# KHNfilter.net
KiCad netlist of a schematic drawn in Altium Designer
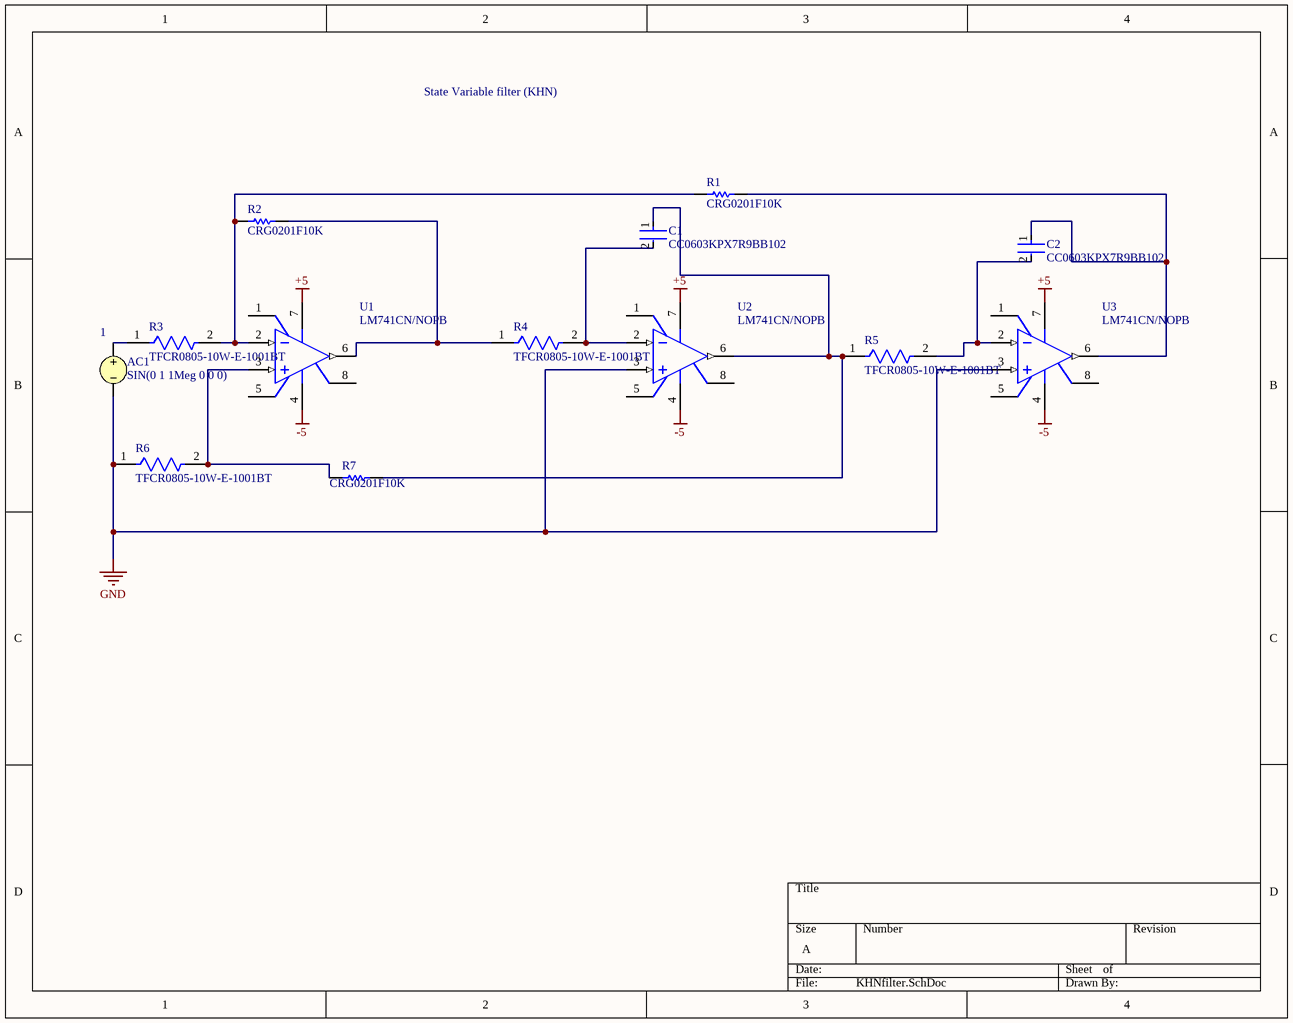
[diagram p0: KHNfilter.SchDoc]

(export (version "E")
  (design (tool "Eeschema 10.0.6"))
  (components
    (comp (ref "AC1")
      (value "SIN(0 1 1Meg 0 0 0)")
      (description "Voltage Source")
      (fields (field (name "AC MAGNITUDE") "1") (field (name "PUBLISHER") "Altium Limited"))
      (libsource (lib "Simulation Generic Components") (part "VSRC"))
    )
    (comp (ref "C1")
      (value "CC0603KPX7R9BB102")
      (footprint "FP-CC0603-DA-MFG")
      (description "CC0603 1.0 nF X7R 10.00% 50 V")
      (fields (field (name "VOLTAGE") "50 V") (field (name "TOLERANCE") "0.1"))
      (libsource (lib "Altium Content Vault") (part "11868f565c42a9108669ba33697ecf6"))
    )
    (comp (ref "C2")
      (value "CC0603KPX7R9BB102")
      (footprint "FP-CC0603-DA-MFG")
      (description "CC0603 1.0 nF X7R 10.00% 50 V")
      (fields (field (name "VOLTAGE") "50 V") (field (name "TOLERANCE") "0.1"))
      (libsource (lib "Altium Content Vault") (part "11868f565c42a9108669ba33697ecf6"))
    )
    (comp (ref "R1")
      (value "CRG0201F10K")
      (footprint "RESC0603X26X15LL03T05")
      (fields (field (name "MANUFACTURER") "TE Connectivity / AMP"))
      (libsource (lib "Altium Content Vault") (part "RES"))
    )
    (comp (ref "R2")
      (value "CRG0201F10K")
      (footprint "RESC0603X26X15LL03T05")
      (fields (field (name "MANUFACTURER") "TE Connectivity / AMP"))
      (libsource (lib "Altium Content Vault") (part "RES"))
    )
    (comp (ref "R3")
      (value "TFCR0805-10W-E-1001BT")
      (footprint "FP-TFCR0805-IPC_A")
      (description "RES Thin Film,  1kΩ, 0.1%, 0.1W, 25ppm/°C, 0805")
      (libsource (lib "Altium Content Vault") (part "1029c3af85768c4190bb7ad29bc67b5"))
    )
    (comp (ref "R4")
      (value "TFCR0805-10W-E-1001BT")
      (footprint "FP-TFCR0805-IPC_A")
      (description "RES Thin Film,  1kΩ, 0.1%, 0.1W, 25ppm/°C, 0805")
      (libsource (lib "Altium Content Vault") (part "1029c3af85768c4190bb7ad29bc67b5"))
    )
    (comp (ref "R5")
      (value "TFCR0805-10W-E-1001BT")
      (footprint "FP-TFCR0805-IPC_A")
      (description "RES Thin Film,  1kΩ, 0.1%, 0.1W, 25ppm/°C, 0805")
      (libsource (lib "Altium Content Vault") (part "1029c3af85768c4190bb7ad29bc67b5"))
    )
    (comp (ref "R6")
      (value "TFCR0805-10W-E-1001BT")
      (footprint "FP-TFCR0805-IPC_A")
      (description "RES Thin Film,  1kΩ, 0.1%, 0.1W, 25ppm/°C, 0805")
      (libsource (lib "Altium Content Vault") (part "1029c3af85768c4190bb7ad29bc67b5"))
    )
    (comp (ref "R7")
      (value "CRG0201F10K")
      (footprint "RESC0603X26X15LL03T05")
      (fields (field (name "MANUFACTURER") "TE Connectivity / AMP"))
      (libsource (lib "Altium Content Vault") (part "RES"))
    )
    (comp (ref "U1")
      (value "LM741CN/NOPB")
      (footprint "P0008A")
      (description "Operational Amplifier, 8-pin MDIP, Pb-Free")
      (fields (field (name "MANUFACTURER") "Texas Instruments"))
      (libsource (lib "Altium Content Vault") (part "AMP-OPA-LM741-8"))
    )
    (comp (ref "U2")
      (value "LM741CN/NOPB")
      (footprint "P0008A")
      (description "Operational Amplifier, 8-pin MDIP, Pb-Free")
      (fields (field (name "MANUFACTURER") "Texas Instruments"))
      (libsource (lib "Altium Content Vault") (part "AMP-OPA-LM741-8"))
    )
    (comp (ref "U3")
      (value "LM741CN/NOPB")
      (footprint "P0008A")
      (description "Operational Amplifier, 8-pin MDIP, Pb-Free")
      (fields (field (name "MANUFACTURER") "Texas Instruments"))
      (libsource (lib "Altium Content Vault") (part "AMP-OPA-LM741-8"))
    )
  )
  (nets
    (net (code "1") (name "+5") (class "Default")
      (node (ref "U1") (pin "7") (pinfunction "V+_7") (pintype "power_in"))
      (node (ref "U2") (pin "7") (pinfunction "V+_7") (pintype "power_in"))
      (node (ref "U3") (pin "7") (pinfunction "V+_7") (pintype "power_in"))
    )
    (net (code "2") (name "-5") (class "Default")
      (node (ref "U1") (pin "4") (pinfunction "V-_4") (pintype "power_in"))
      (node (ref "U2") (pin "4") (pinfunction "V-_4") (pintype "power_in"))
      (node (ref "U3") (pin "4") (pinfunction "V-_4") (pintype "power_in"))
    )
    (net (code "3") (name "GND") (class "Default")
      (node (ref "AC1") (pin "2") (pinfunction "2_2") (pintype "passive"))
      (node (ref "R6") (pin "1") (pinfunction "1_1") (pintype "passive"))
      (node (ref "U2") (pin "3") (pinfunction "IN+_3") (pintype "input"))
      (node (ref "U3") (pin "3") (pinfunction "IN+_3") (pintype "input"))
    )
    (net (code "4") (name "Net-(AC1-Pad1)") (class "Default")
      (node (ref "AC1") (pin "1") (pinfunction "1_1") (pintype "passive"))
      (node (ref "R3") (pin "1") (pinfunction "1_1") (pintype "passive"))
    )
    (net (code "5") (name "Net-(U1-IN+)") (class "Default")
      (node (ref "R6") (pin "2") (pinfunction "2_2") (pintype "passive"))
      (node (ref "R7") (pin "1") (pinfunction "1_1") (pintype "passive"))
      (node (ref "U1") (pin "3") (pinfunction "IN+_3") (pintype "input"))
    )
    (net (code "6") (name "Net-(U1-IN-)") (class "Default")
      (node (ref "R1") (pin "1") (pinfunction "1_1") (pintype "passive"))
      (node (ref "R2") (pin "1") (pinfunction "1_1") (pintype "passive"))
      (node (ref "R3") (pin "2") (pinfunction "2_2") (pintype "passive"))
      (node (ref "U1") (pin "2") (pinfunction "IN-_2") (pintype "input"))
    )
    (net (code "7") (name "Net-(U1-OUT)") (class "Default")
      (node (ref "R2") (pin "2") (pinfunction "2_2") (pintype "passive"))
      (node (ref "R4") (pin "1") (pinfunction "1_1") (pintype "passive"))
      (node (ref "U1") (pin "6") (pinfunction "OUT_6") (pintype "output"))
    )
    (net (code "8") (name "Net-(U2-IN-)") (class "Default")
      (node (ref "C1") (pin "2") (pinfunction "2_2") (pintype "passive"))
      (node (ref "R4") (pin "2") (pinfunction "2_2") (pintype "passive"))
      (node (ref "U2") (pin "2") (pinfunction "IN-_2") (pintype "input"))
    )
    (net (code "9") (name "Net-(U2-OUT)") (class "Default")
      (node (ref "C1") (pin "1") (pinfunction "1_1") (pintype "passive"))
      (node (ref "R5") (pin "1") (pinfunction "1_1") (pintype "passive"))
      (node (ref "R7") (pin "2") (pinfunction "2_2") (pintype "passive"))
      (node (ref "U2") (pin "6") (pinfunction "OUT_6") (pintype "output"))
    )
    (net (code "10") (name "Net-(U3-IN-)") (class "Default")
      (node (ref "C2") (pin "2") (pinfunction "2_2") (pintype "passive"))
      (node (ref "R5") (pin "2") (pinfunction "2_2") (pintype "passive"))
      (node (ref "U3") (pin "2") (pinfunction "IN-_2") (pintype "input"))
    )
    (net (code "11") (name "Net-(U3-OUT)") (class "Default")
      (node (ref "C2") (pin "1") (pinfunction "1_1") (pintype "passive"))
      (node (ref "R1") (pin "2") (pinfunction "2_2") (pintype "passive"))
      (node (ref "U3") (pin "6") (pinfunction "OUT_6") (pintype "output"))
    )
    (net (code "12") (name "unconnected-(U1-NC-Pad8)") (class "Default")
      (node (ref "U1") (pin "8") (pinfunction "NC_8") (pintype "passive"))
    )
    (net (code "13") (name "unconnected-(U1-OFS_NULL-Pad1)") (class "Default")
      (node (ref "U1") (pin "1") (pinfunction "OFS_NULL_1") (pintype "passive"))
    )
    (net (code "14") (name "unconnected-(U1-OFS_NULL-Pad5)") (class "Default")
      (node (ref "U1") (pin "5") (pinfunction "OFS_NULL_5") (pintype "passive"))
    )
    (net (code "15") (name "unconnected-(U2-NC-Pad8)") (class "Default")
      (node (ref "U2") (pin "8") (pinfunction "NC_8") (pintype "passive"))
    )
    (net (code "16") (name "unconnected-(U2-OFS_NULL-Pad1)") (class "Default")
      (node (ref "U2") (pin "1") (pinfunction "OFS_NULL_1") (pintype "passive"))
    )
    (net (code "17") (name "unconnected-(U2-OFS_NULL-Pad5)") (class "Default")
      (node (ref "U2") (pin "5") (pinfunction "OFS_NULL_5") (pintype "passive"))
    )
    (net (code "18") (name "unconnected-(U3-NC-Pad8)") (class "Default")
      (node (ref "U3") (pin "8") (pinfunction "NC_8") (pintype "passive"))
    )
    (net (code "19") (name "unconnected-(U3-OFS_NULL-Pad1)") (class "Default")
      (node (ref "U3") (pin "1") (pinfunction "OFS_NULL_1") (pintype "passive"))
    )
    (net (code "20") (name "unconnected-(U3-OFS_NULL-Pad5)") (class "Default")
      (node (ref "U3") (pin "5") (pinfunction "OFS_NULL_5") (pintype "passive"))
    )
  )
)
